# 1-Schematic_ProjetoSemestral.net
KiCad netlist of a schematic drawn in EasyEDA
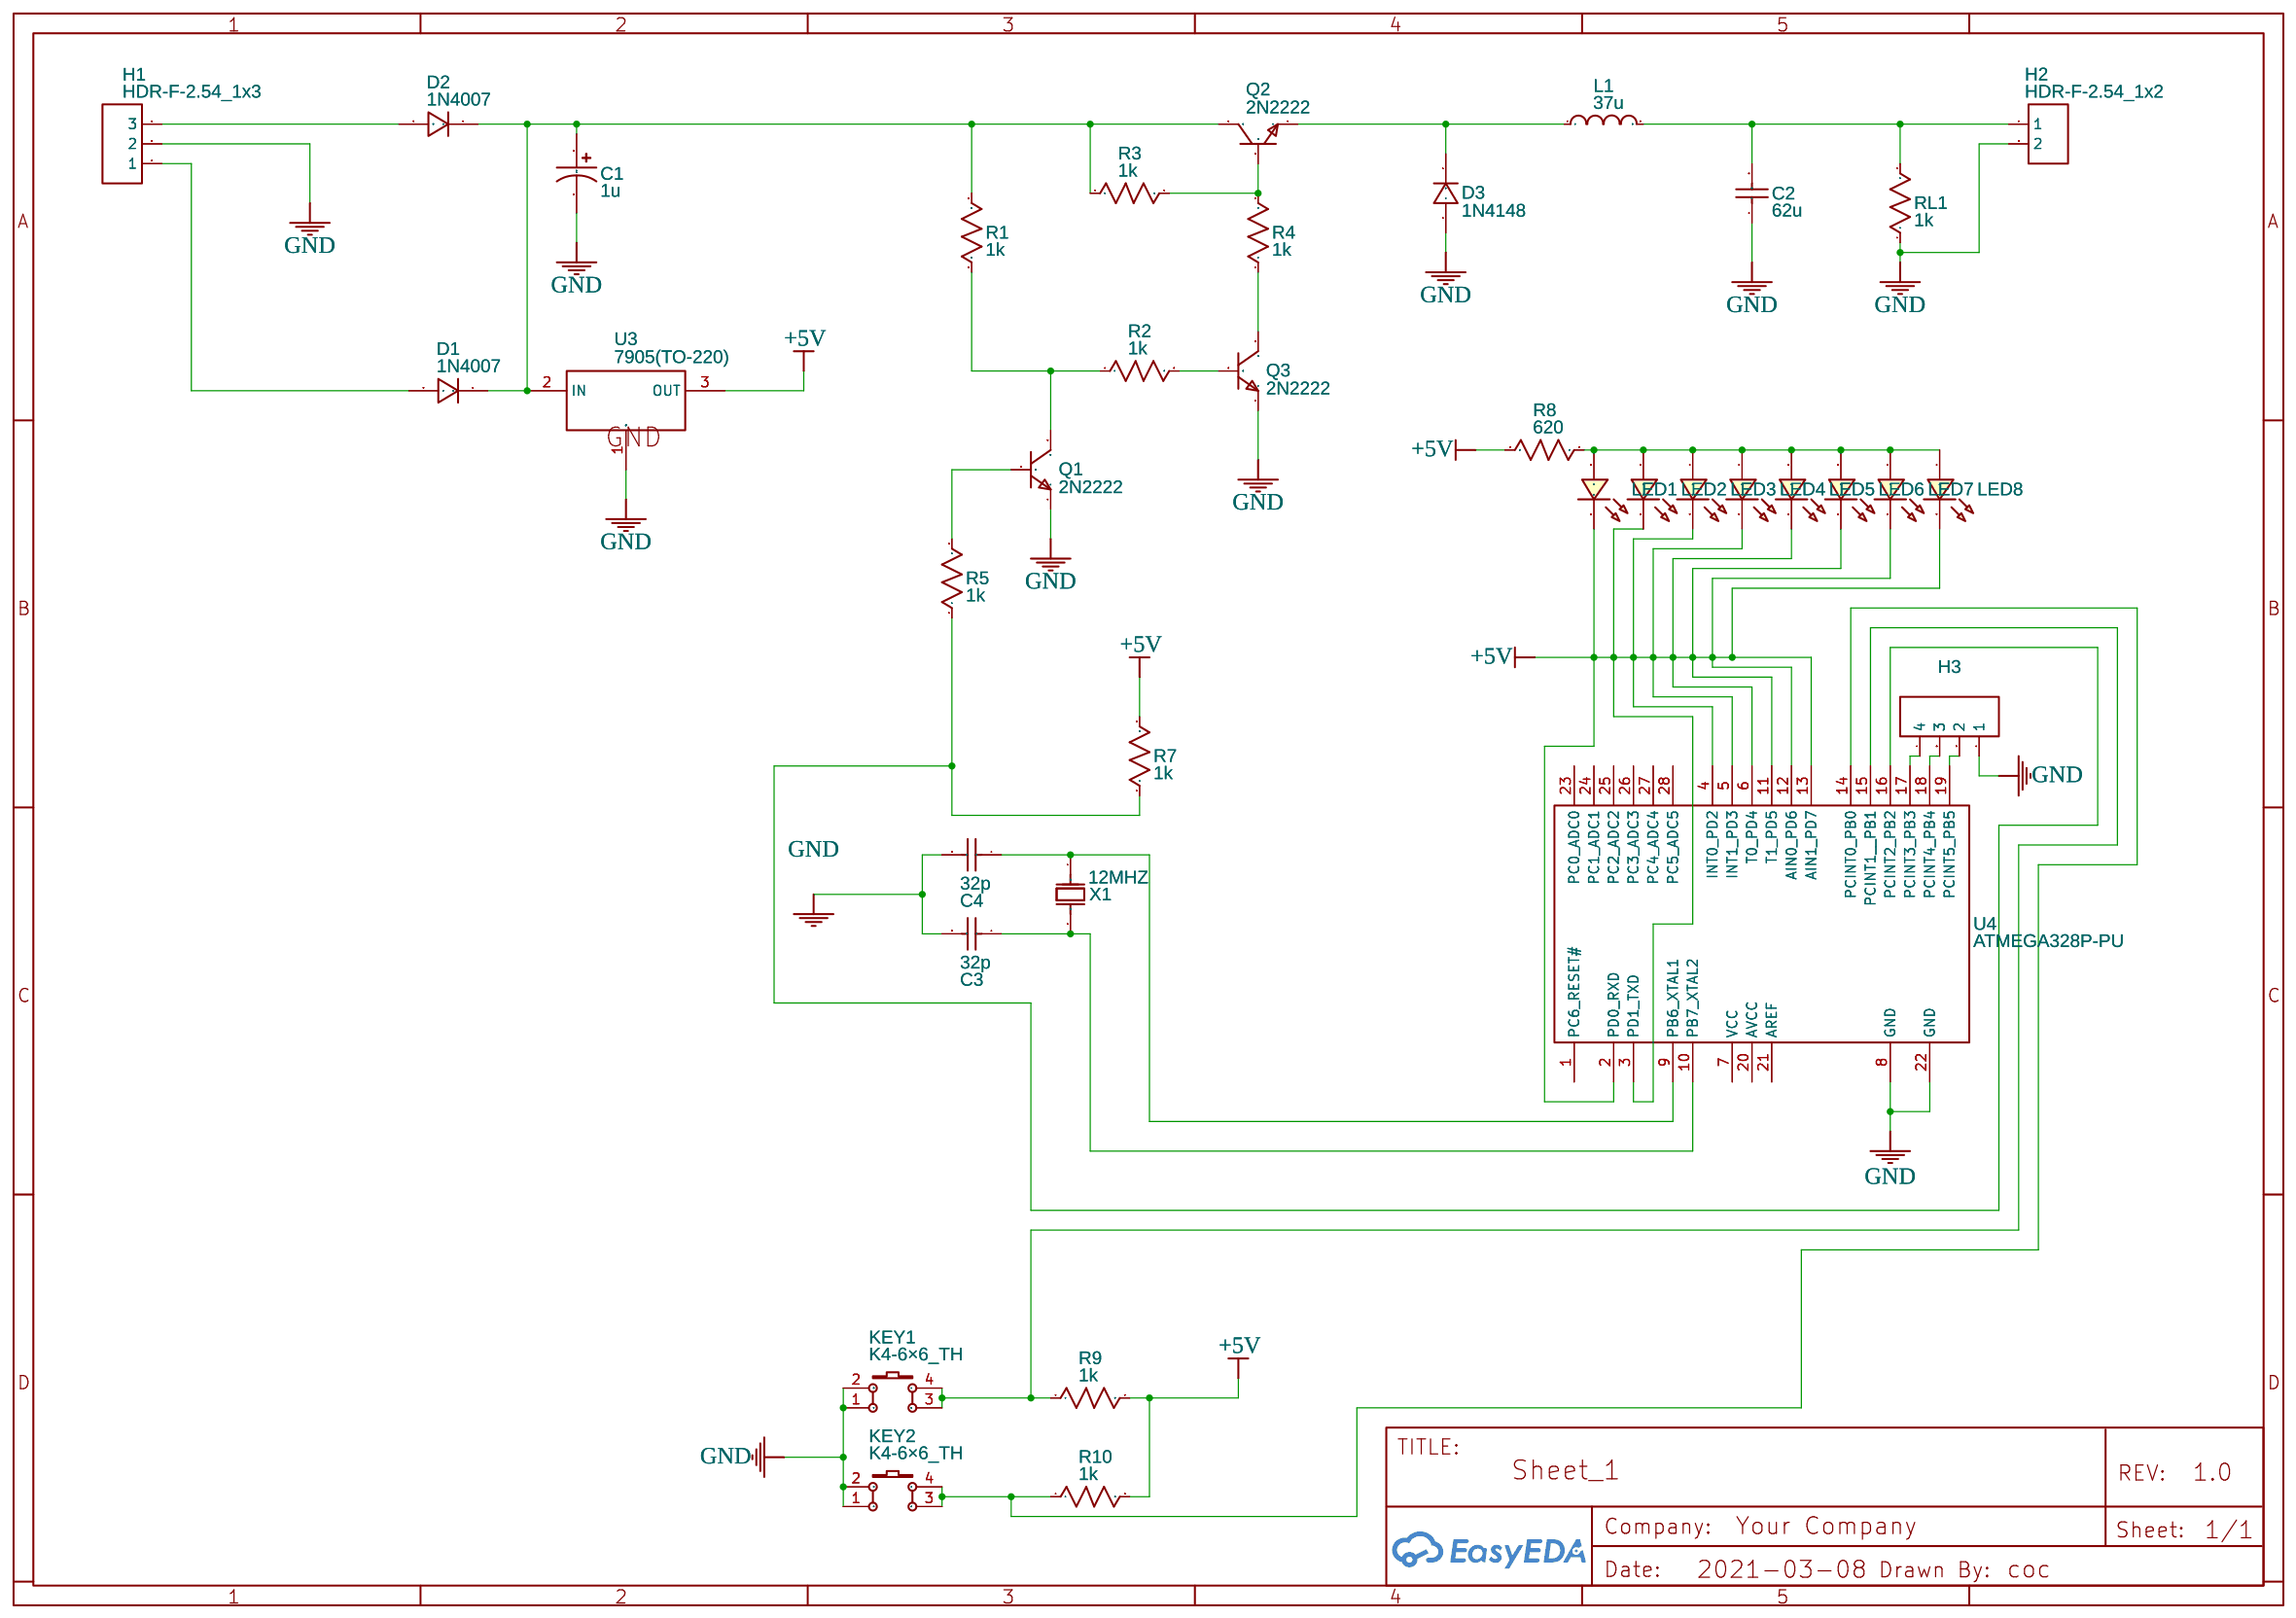
[diagram p0: schematic sheet]

(export (version "E")
  (design (tool "Eeschema 10.0.6"))
  (components
    (comp (ref "C1") (value "1u") (libsource (lib "") (part "CE_TH_D3.0×F1.5_US")))
    (comp (ref "C2")
      (value "62u")
      (fields
        (field (name "BOM_Manufacturer Part") "Capacitor15nf100v")
        (field (name "BOM_Supplier Part") "C26191")
      )
      (libsource (lib "") (part "CAPACITOR15NF100V_1"))
    )
    (comp (ref "C3")
      (value "32p")
      (fields
        (field (name "BOM_Manufacturer Part") "Capacitor15nf100v")
        (field (name "BOM_Supplier Part") "C26191")
      )
      (libsource (lib "") (part "CAPACITOR15NF100V"))
    )
    (comp (ref "C4")
      (value "32p")
      (fields
        (field (name "BOM_Manufacturer Part") "Capacitor15nf100v")
        (field (name "BOM_Supplier Part") "C26191")
      )
      (libsource (lib "") (part "CAPACITOR15NF100V"))
    )
    (comp (ref "D1")
      (value "1N4007")
      (fields (field (name "BOM_Supplier Part") "C106903"))
      (libsource (lib "") (part "1N4007"))
    )
    (comp (ref "D2")
      (value "1N4007")
      (fields (field (name "BOM_Supplier Part") "C106903"))
      (libsource (lib "") (part "1N4007"))
    )
    (comp (ref "D3")
      (value "1N4148")
      (fields (field (name "BOM_Supplier Part") "C14516"))
      (libsource (lib "") (part "1N4148"))
    )
    (comp (ref "H1")
      (value "HDR-F-2.54_1x3")
      (fields (field (name "BOM_Supplier Part") "C146690"))
      (libsource (lib "") (part "HDR-F-2.54_1x3"))
    )
    (comp (ref "H2")
      (value "HDR-F-2.54_1x2")
      (fields (field (name "BOM_Supplier Part") "C49661"))
      (libsource (lib "") (part "HDR-F-2.54_1x2"))
    )
    (comp (ref "H3")
      (value "HDR-F-2.54_1x4")
      (fields (field (name "BOM_Supplier Part") "C225501"))
      (libsource (lib "") (part "HDR-F-2.54_1x4"))
    )
    (comp (ref "KEY1")
      (value "K4-6×6_TH")
      (fields
        (field (name "BOM_Manufacturer Part") "K2-1102DP-E4SW-04")
        (field (name "BOM_Supplier Part") "C136684")
      )
      (libsource (lib "") (part "K4-6×6_TH"))
    )
    (comp (ref "KEY2")
      (value "K4-6×6_TH")
      (fields
        (field (name "BOM_Manufacturer Part") "K2-1102DP-E4SW-04")
        (field (name "BOM_Supplier Part") "C136684")
      )
      (libsource (lib "") (part "K4-6×6_TH"))
    )
    (comp (ref "L1") (value "37u") (libsource (lib "") (part "L_AXIAL-0.4_US")))
    (comp (ref "LED1")
      (value "LED-TH-3mm_R")
      (fields
        (field (name "BOM_Manufacturer Part") "204-10SDRD/S530-A3-L")
        (field (name "BOM_Supplier Part") "C84774")
      )
      (libsource (lib "") (part "LED-TH-3mm_R"))
    )
    (comp (ref "LED2")
      (value "LED-TH-3mm_R")
      (fields
        (field (name "BOM_Manufacturer Part") "204-10SDRD/S530-A3-L")
        (field (name "BOM_Supplier Part") "C84774")
      )
      (libsource (lib "") (part "LED-TH-3mm_R"))
    )
    (comp (ref "LED3")
      (value "LED-TH-3mm_R")
      (fields
        (field (name "BOM_Manufacturer Part") "204-10SDRD/S530-A3-L")
        (field (name "BOM_Supplier Part") "C84774")
      )
      (libsource (lib "") (part "LED-TH-3mm_R"))
    )
    (comp (ref "LED4")
      (value "LED-TH-3mm_R")
      (fields
        (field (name "BOM_Manufacturer Part") "204-10SDRD/S530-A3-L")
        (field (name "BOM_Supplier Part") "C84774")
      )
      (libsource (lib "") (part "LED-TH-3mm_R"))
    )
    (comp (ref "LED5")
      (value "LED-TH-3mm_R")
      (fields
        (field (name "BOM_Manufacturer Part") "204-10SDRD/S530-A3-L")
        (field (name "BOM_Supplier Part") "C84774")
      )
      (libsource (lib "") (part "LED-TH-3mm_R"))
    )
    (comp (ref "LED6")
      (value "LED-TH-3mm_R")
      (fields
        (field (name "BOM_Manufacturer Part") "204-10SDRD/S530-A3-L")
        (field (name "BOM_Supplier Part") "C84774")
      )
      (libsource (lib "") (part "LED-TH-3mm_R"))
    )
    (comp (ref "LED7")
      (value "LED-TH-3mm_R")
      (fields
        (field (name "BOM_Manufacturer Part") "204-10SDRD/S530-A3-L")
        (field (name "BOM_Supplier Part") "C84774")
      )
      (libsource (lib "") (part "LED-TH-3mm_R"))
    )
    (comp (ref "LED8")
      (value "LED-TH-3mm_R")
      (fields
        (field (name "BOM_Manufacturer Part") "204-10SDRD/S530-A3-L")
        (field (name "BOM_Supplier Part") "C84774")
      )
      (libsource (lib "") (part "LED-TH-3mm_R"))
    )
    (comp (ref "Q1")
      (value "2N2222")
      (fields (field (name "BOM_Supplier Part") "C118536"))
      (libsource (lib "") (part "2N2222_1"))
    )
    (comp (ref "Q2")
      (value "2N2222")
      (fields (field (name "BOM_Supplier Part") "C118536"))
      (libsource (lib "") (part "2N2222"))
    )
    (comp (ref "Q3")
      (value "2N2222")
      (fields (field (name "BOM_Supplier Part") "C118536"))
      (libsource (lib "") (part "2N2222_1"))
    )
    (comp (ref "R1") (value "1k") (libsource (lib "") (part "R_AXIAL-0.3_US_1")))
    (comp (ref "R2") (value "1k") (libsource (lib "") (part "R_AXIAL-0.3_US")))
    (comp (ref "R3") (value "1k") (libsource (lib "") (part "R_AXIAL-0.3_US")))
    (comp (ref "R4") (value "1k") (libsource (lib "") (part "R_AXIAL-0.3_US_1")))
    (comp (ref "R5") (value "1k") (libsource (lib "") (part "R_AXIAL-0.3_US_1")))
    (comp (ref "R7") (value "1k") (libsource (lib "") (part "R_AXIAL-0.3_US_1")))
    (comp (ref "R8") (value "620") (libsource (lib "") (part "R_AXIAL-0.3_US_2")))
    (comp (ref "R9") (value "1k") (libsource (lib "") (part "R_AXIAL-0.3_US")))
    (comp (ref "R10") (value "1k") (libsource (lib "") (part "R_AXIAL-0.3_US")))
    (comp (ref "RL1") (value "1k") (libsource (lib "") (part "R_AXIAL-0.3_US_3")))
    (comp (ref "U3")
      (value "7905(TO-220)")
      (fields (field (name "BOM_Manufacturer Part") "L7905CV-DG") (field (name "BOM_Supplier Part") "C3799"))
      (libsource (lib "") (part "7905(TO-220)"))
    )
    (comp (ref "U4")
      (value "ATMEGA328P-PU")
      (fields (field (name "BOM_Supplier Part") "C33901"))
      (libsource (lib "") (part "ATMEGA328P-PU"))
    )
    (comp (ref "X1")
      (value "12MHZ")
      (fields
        (field (name "BOM_Manufacturer Part") "49SAC12000202060")
        (field (name "BOM_Supplier Part") "C390746")
      )
      (libsource (lib "") (part "49SAC12000202060"))
    )
  )
  (nets
    (net (code "1") (name "+5V") (class "Default")
      (node (ref "LED1") (pin "2") (pinfunction "2_2") (pintype "unspecified"))
      (node (ref "LED2") (pin "2") (pinfunction "2_2") (pintype "unspecified"))
      (node (ref "LED3") (pin "2") (pinfunction "2_2") (pintype "unspecified"))
      (node (ref "LED4") (pin "2") (pinfunction "2_2") (pintype "unspecified"))
      (node (ref "LED5") (pin "2") (pinfunction "2_2") (pintype "unspecified"))
      (node (ref "LED6") (pin "2") (pinfunction "2_2") (pintype "unspecified"))
      (node (ref "LED7") (pin "2") (pinfunction "2_2") (pintype "unspecified"))
      (node (ref "LED8") (pin "2") (pinfunction "2_2") (pintype "unspecified"))
      (node (ref "R10") (pin "2") (pinfunction "2_2") (pintype "unspecified"))
      (node (ref "R7") (pin "2") (pinfunction "2_2") (pintype "unspecified"))
      (node (ref "R8") (pin "2") (pinfunction "2_2") (pintype "unspecified"))
      (node (ref "R9") (pin "2") (pinfunction "2_2") (pintype "unspecified"))
      (node (ref "U3") (pin "3") (pinfunction "OUT_3") (pintype "passive"))
      (node (ref "U4") (pin "11") (pinfunction "T1_PD5_11") (pintype "bidirectional"))
      (node (ref "U4") (pin "12") (pinfunction "AIN0_PD6_12") (pintype "bidirectional"))
      (node (ref "U4") (pin "13") (pinfunction "AIN1_PD7_13") (pintype "bidirectional"))
      (node (ref "U4") (pin "2") (pinfunction "PD0_RXD_2") (pintype "bidirectional"))
      (node (ref "U4") (pin "3") (pinfunction "PD1_TXD_3") (pintype "bidirectional"))
      (node (ref "U4") (pin "4") (pinfunction "INT0_PD2_4") (pintype "bidirectional"))
      (node (ref "U4") (pin "5") (pinfunction "INT1_PD3_5") (pintype "bidirectional"))
      (node (ref "U4") (pin "6") (pinfunction "T0_PD4_6") (pintype "bidirectional"))
    )
    (net (code "2") (name "GND") (class "Default")
      (node (ref "C1") (pin "2") (pinfunction "2_2") (pintype "unspecified"))
      (node (ref "C2") (pin "1") (pinfunction "1_1") (pintype "input"))
      (node (ref "C3") (pin "2") (pinfunction "2_2") (pintype "input"))
      (node (ref "C4") (pin "2") (pinfunction "2_2") (pintype "input"))
      (node (ref "D3") (pin "1") (pinfunction "1_1") (pintype "unspecified"))
      (node (ref "H1") (pin "2") (pinfunction "2_2") (pintype "input"))
      (node (ref "H2") (pin "2") (pinfunction "2_2") (pintype "input"))
      (node (ref "H3") (pin "1") (pinfunction "1_1") (pintype "unspecified"))
      (node (ref "KEY1") (pin "1") (pinfunction "1_1") (pintype "unspecified"))
      (node (ref "KEY1") (pin "2") (pinfunction "2_2") (pintype "unspecified"))
      (node (ref "KEY2") (pin "1") (pinfunction "1_1") (pintype "unspecified"))
      (node (ref "KEY2") (pin "2") (pinfunction "2_2") (pintype "unspecified"))
      (node (ref "Q1") (pin "1") (pinfunction "E_1") (pintype "unspecified"))
      (node (ref "Q3") (pin "1") (pinfunction "E_1") (pintype "unspecified"))
      (node (ref "RL1") (pin "1") (pinfunction "1_1") (pintype "unspecified"))
      (node (ref "U3") (pin "1") (pinfunction "GND_1") (pintype "passive"))
      (node (ref "U4") (pin "22") (pinfunction "GND_22") (pintype "passive"))
      (node (ref "U4") (pin "8") (pinfunction "GND_8") (pintype "passive"))
    )
    (net (code "3") (name "Net-(C2-Pad2)") (class "Default")
      (node (ref "C2") (pin "2") (pinfunction "2_2") (pintype "input"))
      (node (ref "H2") (pin "1") (pinfunction "1_1") (pintype "input"))
      (node (ref "L1") (pin "2") (pinfunction "2_2") (pintype "unspecified"))
      (node (ref "RL1") (pin "2") (pinfunction "2_2") (pintype "unspecified"))
    )
    (net (code "4") (name "Net-(D1-Pad2)") (class "Default")
      (node (ref "D1") (pin "2") (pinfunction "2_2") (pintype "unspecified"))
      (node (ref "H1") (pin "1") (pinfunction "1_1") (pintype "input"))
    )
    (net (code "5") (name "Net-(D2-Pad2)") (class "Default")
      (node (ref "D2") (pin "2") (pinfunction "2_2") (pintype "unspecified"))
      (node (ref "H1") (pin "3") (pinfunction "3_3") (pintype "input"))
    )
    (net (code "6") (name "Net-(LED1-Pad1)") (class "Default")
      (node (ref "LED1") (pin "1") (pinfunction "1_1") (pintype "unspecified"))
      (node (ref "LED2") (pin "1") (pinfunction "1_1") (pintype "unspecified"))
      (node (ref "LED3") (pin "1") (pinfunction "1_1") (pintype "unspecified"))
      (node (ref "LED4") (pin "1") (pinfunction "1_1") (pintype "unspecified"))
      (node (ref "LED5") (pin "1") (pinfunction "1_1") (pintype "unspecified"))
      (node (ref "LED6") (pin "1") (pinfunction "1_1") (pintype "unspecified"))
      (node (ref "LED7") (pin "1") (pinfunction "1_1") (pintype "unspecified"))
      (node (ref "LED8") (pin "1") (pinfunction "1_1") (pintype "unspecified"))
      (node (ref "R8") (pin "1") (pinfunction "1_1") (pintype "unspecified"))
    )
    (net (code "7") (name "Net-(Q1-B)") (class "Default")
      (node (ref "Q1") (pin "2") (pinfunction "B_2") (pintype "unspecified"))
      (node (ref "R5") (pin "2") (pinfunction "2_2") (pintype "unspecified"))
    )
    (net (code "8") (name "Net-(Q1-C)") (class "Default")
      (node (ref "Q1") (pin "3") (pinfunction "C_3") (pintype "unspecified"))
      (node (ref "R1") (pin "1") (pinfunction "1_1") (pintype "unspecified"))
      (node (ref "R2") (pin "1") (pinfunction "1_1") (pintype "unspecified"))
    )
    (net (code "9") (name "Net-(Q2-B)") (class "Default")
      (node (ref "Q2") (pin "2") (pinfunction "B_2") (pintype "unspecified"))
      (node (ref "R3") (pin "2") (pinfunction "2_2") (pintype "unspecified"))
      (node (ref "R4") (pin "2") (pinfunction "2_2") (pintype "unspecified"))
    )
    (net (code "10") (name "Net-(Q2-C)") (class "Default")
      (node (ref "C1") (pin "1") (pinfunction "1_1") (pintype "unspecified"))
      (node (ref "D1") (pin "1") (pinfunction "1_1") (pintype "unspecified"))
      (node (ref "D2") (pin "1") (pinfunction "1_1") (pintype "unspecified"))
      (node (ref "Q2") (pin "3") (pinfunction "C_3") (pintype "unspecified"))
      (node (ref "R1") (pin "2") (pinfunction "2_2") (pintype "unspecified"))
      (node (ref "R3") (pin "1") (pinfunction "1_1") (pintype "unspecified"))
      (node (ref "U3") (pin "2") (pinfunction "IN_2") (pintype "passive"))
    )
    (net (code "11") (name "Net-(Q2-E)") (class "Default")
      (node (ref "D3") (pin "2") (pinfunction "2_2") (pintype "unspecified"))
      (node (ref "L1") (pin "1") (pinfunction "1_1") (pintype "unspecified"))
      (node (ref "Q2") (pin "1") (pinfunction "E_1") (pintype "unspecified"))
    )
    (net (code "12") (name "Net-(Q3-B)") (class "Default")
      (node (ref "Q3") (pin "2") (pinfunction "B_2") (pintype "unspecified"))
      (node (ref "R2") (pin "2") (pinfunction "2_2") (pintype "unspecified"))
    )
    (net (code "13") (name "Net-(Q3-C)") (class "Default")
      (node (ref "Q3") (pin "3") (pinfunction "C_3") (pintype "unspecified"))
      (node (ref "R4") (pin "1") (pinfunction "1_1") (pintype "unspecified"))
    )
    (net (code "14") (name "Net-(U4-PB6_XTAL1)") (class "Default")
      (node (ref "C4") (pin "1") (pinfunction "1_1") (pintype "input"))
      (node (ref "U4") (pin "9") (pinfunction "PB6_XTAL1_9") (pintype "bidirectional"))
      (node (ref "X1") (pin "1") (pinfunction "OSC1_1") (pintype "input"))
    )
    (net (code "15") (name "Net-(U4-PB7_XTAL2)") (class "Default")
      (node (ref "C3") (pin "1") (pinfunction "1_1") (pintype "input"))
      (node (ref "U4") (pin "10") (pinfunction "PB7_XTAL2_10") (pintype "bidirectional"))
      (node (ref "X1") (pin "2") (pinfunction "OSC2_2") (pintype "input"))
    )
    (net (code "16") (name "Net-(U4-PCINT0_PB0)") (class "Default")
      (node (ref "KEY2") (pin "3") (pinfunction "3_3") (pintype "unspecified"))
      (node (ref "KEY2") (pin "4") (pinfunction "4_4") (pintype "unspecified"))
      (node (ref "R10") (pin "1") (pinfunction "1_1") (pintype "unspecified"))
      (node (ref "U4") (pin "14") (pinfunction "PCINT0_PB0_14") (pintype "bidirectional"))
    )
    (net (code "17") (name "Net-(U4-PCINT1__PB1)") (class "Default")
      (node (ref "KEY1") (pin "3") (pinfunction "3_3") (pintype "unspecified"))
      (node (ref "KEY1") (pin "4") (pinfunction "4_4") (pintype "unspecified"))
      (node (ref "R9") (pin "1") (pinfunction "1_1") (pintype "unspecified"))
      (node (ref "U4") (pin "15") (pinfunction "PCINT1__PB1_15") (pintype "bidirectional"))
    )
    (net (code "18") (name "Net-(U4-PCINT2_PB2)") (class "Default")
      (node (ref "R5") (pin "1") (pinfunction "1_1") (pintype "unspecified"))
      (node (ref "R7") (pin "1") (pinfunction "1_1") (pintype "unspecified"))
      (node (ref "U4") (pin "16") (pinfunction "PCINT2_PB2_16") (pintype "bidirectional"))
    )
    (net (code "19") (name "Net-(U4-PCINT3_PB3)") (class "Default")
      (node (ref "H3") (pin "4") (pinfunction "4_4") (pintype "unspecified"))
      (node (ref "U4") (pin "17") (pinfunction "PCINT3_PB3_17") (pintype "bidirectional"))
    )
    (net (code "20") (name "Net-(U4-PCINT4_PB4)") (class "Default")
      (node (ref "H3") (pin "3") (pinfunction "3_3") (pintype "unspecified"))
      (node (ref "U4") (pin "18") (pinfunction "PCINT4_PB4_18") (pintype "bidirectional"))
    )
    (net (code "21") (name "Net-(U4-PCINT5_PB5)") (class "Default")
      (node (ref "H3") (pin "2") (pinfunction "2_2") (pintype "unspecified"))
      (node (ref "U4") (pin "19") (pinfunction "PCINT5_PB5_19") (pintype "bidirectional"))
    )
    (net (code "22") (name "unconnected-(U4-AREF-Pad21)") (class "Default")
      (node (ref "U4") (pin "21") (pinfunction "AREF_21") (pintype "passive"))
    )
    (net (code "23") (name "unconnected-(U4-AVCC-Pad20)") (class "Default")
      (node (ref "U4") (pin "20") (pinfunction "AVCC_20") (pintype "passive"))
    )
    (net (code "24") (name "unconnected-(U4-PC0_ADC0-Pad23)") (class "Default")
      (node (ref "U4") (pin "23") (pinfunction "PC0_ADC0_23") (pintype "bidirectional"))
    )
    (net (code "25") (name "unconnected-(U4-PC1_ADC1-Pad24)") (class "Default")
      (node (ref "U4") (pin "24") (pinfunction "PC1_ADC1_24") (pintype "bidirectional"))
    )
    (net (code "26") (name "unconnected-(U4-PC2_ADC2-Pad25)") (class "Default")
      (node (ref "U4") (pin "25") (pinfunction "PC2_ADC2_25") (pintype "bidirectional"))
    )
    (net (code "27") (name "unconnected-(U4-PC3_ADC3-Pad26)") (class "Default")
      (node (ref "U4") (pin "26") (pinfunction "PC3_ADC3_26") (pintype "bidirectional"))
    )
    (net (code "28") (name "unconnected-(U4-PC4_ADC4-Pad27)") (class "Default")
      (node (ref "U4") (pin "27") (pinfunction "PC4_ADC4_27") (pintype "bidirectional"))
    )
    (net (code "29") (name "unconnected-(U4-PC5_ADC5-Pad28)") (class "Default")
      (node (ref "U4") (pin "28") (pinfunction "PC5_ADC5_28") (pintype "bidirectional"))
    )
    (net (code "30") (name "unconnected-(U4-PC6_RESET#-Pad1)") (class "Default")
      (node (ref "U4") (pin "1") (pinfunction "PC6_RESET#_1") (pintype "bidirectional"))
    )
    (net (code "31") (name "unconnected-(U4-VCC-Pad7)") (class "Default")
      (node (ref "U4") (pin "7") (pinfunction "VCC_7") (pintype "passive"))
    )
  )
)
